# Easy-CI-V.net
KiCad netlist of a schematic drawn in EasyEDA
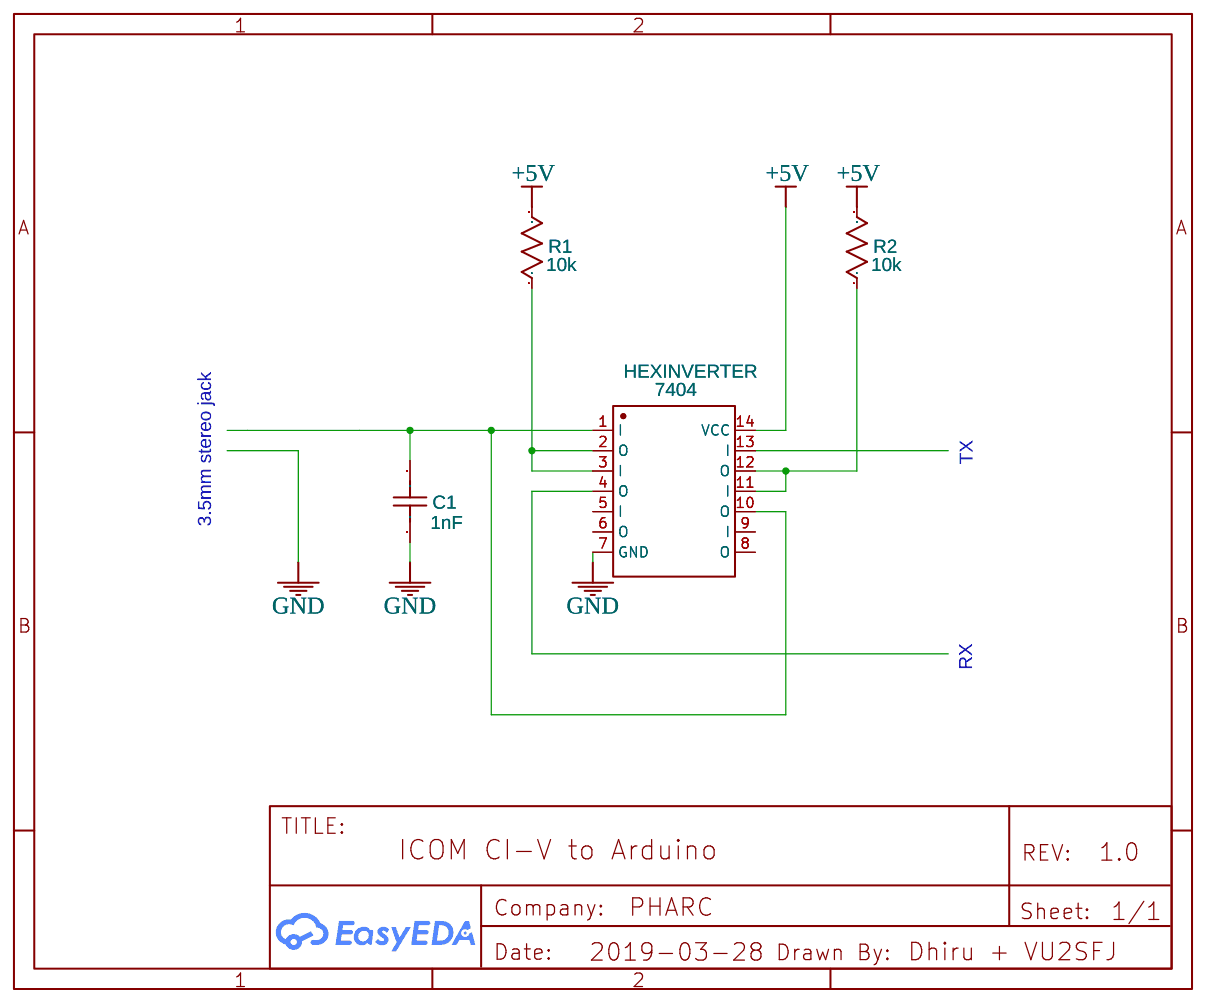
[diagram p0: schematic sheet]

(export (version "E")
  (design (tool "Eeschema 10.0.6"))
  (components
    (comp (ref "C1")
      (value "1nF")
      (fields (field (name "BOM_Manufacturer Part") "?"))
      (libsource (lib "") (part "Cap_RAD-0.1_US"))
    )
    (comp (ref "HEXINVERTER")
      (value "7404")
      (fields (field (name "BOM_Manufacturer Part") "?"))
      (libsource (lib "") (part "Unknown_760_185"))
    )
    (comp (ref "R1")
      (value "10k")
      (fields (field (name "BOM_Manufacturer Part") "?"))
      (libsource (lib "") (part "Res_AXIAL-0.3(1/8W)_US"))
    )
    (comp (ref "R2")
      (value "10k")
      (fields (field (name "BOM_Manufacturer Part") "?"))
      (libsource (lib "") (part "Res_AXIAL-0.3(1/8W)_US"))
    )
  )
  (nets
    (net (code "1") (name "+5V") (class "Default")
      (node (ref "HEXINVERTER") (pin "14") (pinfunction "VCC_14") (pintype "unspecified"))
      (node (ref "R1") (pin "2") (pinfunction "2_2") (pintype "unspecified"))
      (node (ref "R2") (pin "2") (pinfunction "2_2") (pintype "unspecified"))
    )
    (net (code "2") (name "GND") (class "Default")
      (node (ref "C1") (pin "1") (pinfunction "1_1") (pintype "unspecified"))
      (node (ref "HEXINVERTER") (pin "7") (pinfunction "GND_7") (pintype "unspecified"))
    )
    (net (code "3") (name "Net-(C1-Pad2)") (class "Default")
      (node (ref "C1") (pin "2") (pinfunction "2_2") (pintype "unspecified"))
      (node (ref "HEXINVERTER") (pin "1") (pinfunction "I_1") (pintype "unspecified"))
      (node (ref "HEXINVERTER") (pin "10") (pinfunction "O_10") (pintype "unspecified"))
    )
    (net (code "4") (name "Net-(HEXINVERTER-I-Pad3)") (class "Default")
      (node (ref "HEXINVERTER") (pin "2") (pinfunction "O_2") (pintype "unspecified"))
      (node (ref "HEXINVERTER") (pin "3") (pinfunction "I_3") (pintype "unspecified"))
      (node (ref "R1") (pin "1") (pinfunction "1_1") (pintype "unspecified"))
    )
    (net (code "5") (name "Net-(HEXINVERTER-I-Pad11)") (class "Default")
      (node (ref "HEXINVERTER") (pin "11") (pinfunction "I_11") (pintype "unspecified"))
      (node (ref "HEXINVERTER") (pin "12") (pinfunction "O_12") (pintype "unspecified"))
      (node (ref "R2") (pin "1") (pinfunction "1_1") (pintype "unspecified"))
    )
    (net (code "6") (name "unconnected-(HEXINVERTER-I-Pad5)") (class "Default")
      (node (ref "HEXINVERTER") (pin "5") (pinfunction "I_5") (pintype "unspecified"))
    )
    (net (code "7") (name "unconnected-(HEXINVERTER-I-Pad9)") (class "Default")
      (node (ref "HEXINVERTER") (pin "9") (pinfunction "I_9") (pintype "unspecified"))
    )
    (net (code "8") (name "unconnected-(HEXINVERTER-I-Pad13)") (class "Default")
      (node (ref "HEXINVERTER") (pin "13") (pinfunction "I_13") (pintype "unspecified"))
    )
    (net (code "9") (name "unconnected-(HEXINVERTER-O-Pad4)") (class "Default")
      (node (ref "HEXINVERTER") (pin "4") (pinfunction "O_4") (pintype "unspecified"))
    )
    (net (code "10") (name "unconnected-(HEXINVERTER-O-Pad6)") (class "Default")
      (node (ref "HEXINVERTER") (pin "6") (pinfunction "O_6") (pintype "unspecified"))
    )
    (net (code "11") (name "unconnected-(HEXINVERTER-O-Pad8)") (class "Default")
      (node (ref "HEXINVERTER") (pin "8") (pinfunction "O_8") (pintype "unspecified"))
    )
  )
)
